# Day0_Rahmadi_Rizki_S_Pandia.net
KiCad netlist of a schematic drawn in EAGLE
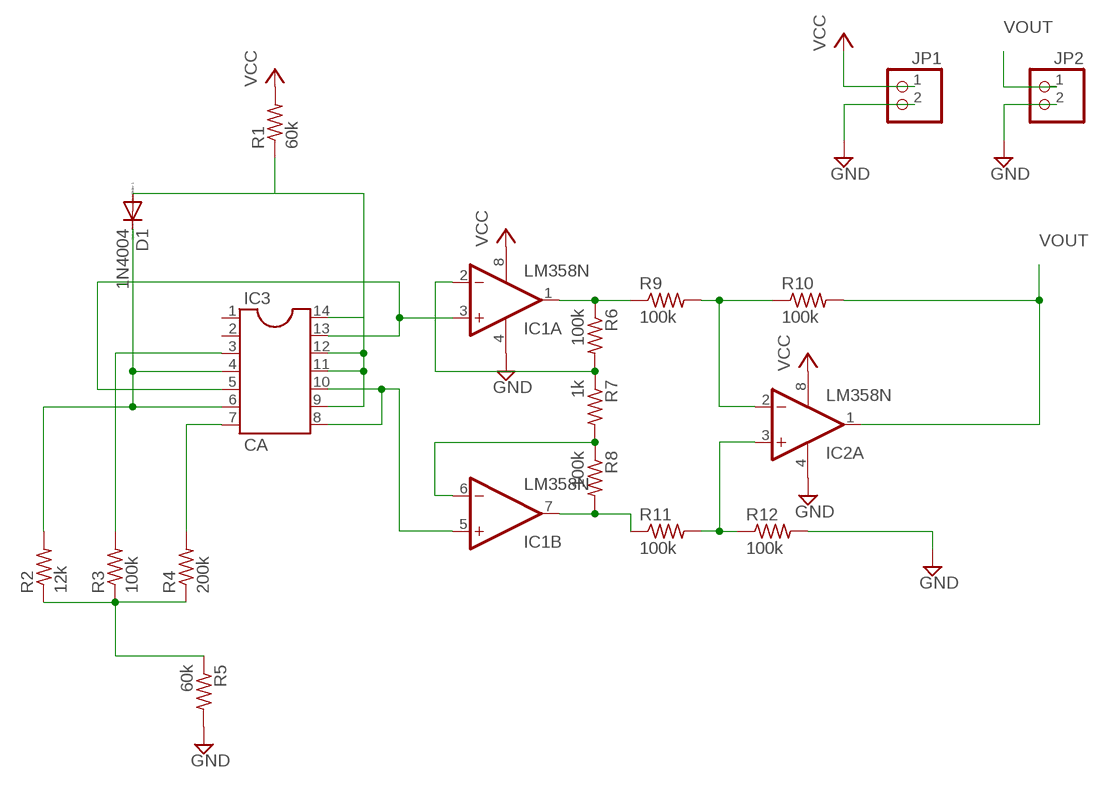
[diagram p0: schematic, sheet 1]

(export (version "E")
  (design (tool "Eeschema 10.0.6"))
  (components
    (comp (ref "D1")
      (value "1N4004")
      (footprint "eagle-import:D-7.5")
      (libsource (lib "eagle-import") (part "DIODE-D-7.5"))
    )
    (comp (ref "IC1")
      (value "LM358N")
      (footprint "eagle-import:DIL08")
      (libsource (lib "eagle-import") (part "LM358N"))
    )
    (comp (ref "IC2")
      (value "LM358N")
      (footprint "eagle-import:DIL08")
      (libsource (lib "eagle-import") (part "LM358N"))
    )
    (comp (ref "IC3")
      (value "CA")
      (footprint "eagle-import:DIL14")
      (libsource (lib "eagle-import") (part "DIL14"))
    )
    (comp (ref "JP1")
      (value "PINHD-1X2")
      (footprint "eagle-import:1X02")
      (libsource (lib "eagle-import") (part "PINHD-1X2"))
    )
    (comp (ref "JP2")
      (value "PINHD-1X2")
      (footprint "eagle-import:1X02")
      (libsource (lib "eagle-import") (part "PINHD-1X2"))
    )
    (comp (ref "R1")
      (value "60k")
      (footprint "eagle-import:0204_7")
      (libsource (lib "eagle-import") (part "R-US_0204/7"))
    )
    (comp (ref "R2")
      (value "12k")
      (footprint "eagle-import:0204_7")
      (libsource (lib "eagle-import") (part "R-US_0204/7"))
    )
    (comp (ref "R3")
      (value "100k")
      (footprint "eagle-import:0204_7")
      (libsource (lib "eagle-import") (part "R-US_0204/7"))
    )
    (comp (ref "R4")
      (value "200k")
      (footprint "eagle-import:0204_7")
      (libsource (lib "eagle-import") (part "R-US_0204/7"))
    )
    (comp (ref "R5")
      (value "60k")
      (footprint "eagle-import:0204_7")
      (libsource (lib "eagle-import") (part "R-US_0204/7"))
    )
    (comp (ref "R6")
      (value "100k")
      (footprint "eagle-import:0204_7")
      (libsource (lib "eagle-import") (part "R-US_0204/7"))
    )
    (comp (ref "R7")
      (value "1k")
      (footprint "eagle-import:0204_7")
      (libsource (lib "eagle-import") (part "R-US_0204/7"))
    )
    (comp (ref "R8")
      (value "100k")
      (footprint "eagle-import:0204_7")
      (libsource (lib "eagle-import") (part "R-US_0204/7"))
    )
    (comp (ref "R9")
      (value "100k")
      (footprint "eagle-import:0204_7")
      (libsource (lib "eagle-import") (part "R-US_0204/7"))
    )
    (comp (ref "R10")
      (value "100k")
      (footprint "eagle-import:0204_7")
      (libsource (lib "eagle-import") (part "R-US_0204/7"))
    )
    (comp (ref "R11")
      (value "100k")
      (footprint "eagle-import:0204_7")
      (libsource (lib "eagle-import") (part "R-US_0204/7"))
    )
    (comp (ref "R12")
      (value "100k")
      (footprint "eagle-import:0204_7")
      (libsource (lib "eagle-import") (part "R-US_0204/7"))
    )
  )
  (nets
    (net (code "1") (name "/VOUT") (class "Default")
      (node (ref "IC2") (pin "1") (pinfunction "OUT_1") (pintype "output"))
      (node (ref "JP2") (pin "1") (pinfunction "1_1") (pintype "passive"))
      (node (ref "R10") (pin "2") (pinfunction "2_2") (pintype "passive"))
    )
    (net (code "2") (name "GND") (class "Default")
      (node (ref "IC1") (pin "4") (pinfunction "V-_4") (pintype "power_in"))
      (node (ref "IC2") (pin "4") (pinfunction "V-_4") (pintype "power_in"))
      (node (ref "JP1") (pin "2") (pinfunction "2_2") (pintype "passive"))
      (node (ref "JP2") (pin "2") (pinfunction "2_2") (pintype "passive"))
      (node (ref "R12") (pin "2") (pinfunction "2_2") (pintype "passive"))
      (node (ref "R5") (pin "2") (pinfunction "2_2") (pintype "passive"))
    )
    (net (code "3") (name "Net-(D1-PadA)") (class "Default")
      (node (ref "D1") (pin "A") (pinfunction "A_A") (pintype "passive"))
      (node (ref "IC3") (pin "11") (pinfunction "11_11") (pintype "passive"))
      (node (ref "IC3") (pin "12") (pinfunction "12_12") (pintype "passive"))
      (node (ref "IC3") (pin "14") (pinfunction "14_14") (pintype "passive"))
      (node (ref "IC3") (pin "9") (pinfunction "9_9") (pintype "passive"))
      (node (ref "R1") (pin "1") (pinfunction "1_1") (pintype "passive"))
    )
    (net (code "4") (name "Net-(D1-PadC)") (class "Default")
      (node (ref "D1") (pin "C") (pinfunction "C_C") (pintype "passive"))
      (node (ref "IC3") (pin "4") (pinfunction "4_4") (pintype "passive"))
      (node (ref "IC3") (pin "6") (pinfunction "6_6") (pintype "passive"))
      (node (ref "R2") (pin "2") (pinfunction "2_2") (pintype "passive"))
    )
    (net (code "5") (name "Net-(IC1A-+IN)") (class "Default")
      (node (ref "IC1") (pin "3") (pinfunction "+IN_3") (pintype "input"))
      (node (ref "IC3") (pin "13") (pinfunction "13_13") (pintype "passive"))
      (node (ref "IC3") (pin "5") (pinfunction "5_5") (pintype "passive"))
    )
    (net (code "6") (name "Net-(IC1A--IN)") (class "Default")
      (node (ref "IC1") (pin "2") (pinfunction "-IN_2") (pintype "input"))
      (node (ref "R6") (pin "2") (pinfunction "2_2") (pintype "passive"))
      (node (ref "R7") (pin "1") (pinfunction "1_1") (pintype "passive"))
    )
    (net (code "7") (name "Net-(IC1A-OUT)") (class "Default")
      (node (ref "IC1") (pin "1") (pinfunction "OUT_1") (pintype "output"))
      (node (ref "R6") (pin "1") (pinfunction "1_1") (pintype "passive"))
      (node (ref "R9") (pin "1") (pinfunction "1_1") (pintype "passive"))
    )
    (net (code "8") (name "Net-(IC1B-+IN)") (class "Default")
      (node (ref "IC1") (pin "5") (pinfunction "+IN_5") (pintype "input"))
      (node (ref "IC3") (pin "10") (pinfunction "10_10") (pintype "passive"))
      (node (ref "IC3") (pin "8") (pinfunction "8_8") (pintype "passive"))
    )
    (net (code "9") (name "Net-(IC1B--IN)") (class "Default")
      (node (ref "IC1") (pin "6") (pinfunction "-IN_6") (pintype "input"))
      (node (ref "R7") (pin "2") (pinfunction "2_2") (pintype "passive"))
      (node (ref "R8") (pin "1") (pinfunction "1_1") (pintype "passive"))
    )
    (net (code "10") (name "Net-(IC1B-OUT)") (class "Default")
      (node (ref "IC1") (pin "7") (pinfunction "OUT_7") (pintype "output"))
      (node (ref "R11") (pin "1") (pinfunction "1_1") (pintype "passive"))
      (node (ref "R8") (pin "2") (pinfunction "2_2") (pintype "passive"))
    )
    (net (code "11") (name "Net-(IC2A-+IN)") (class "Default")
      (node (ref "IC2") (pin "3") (pinfunction "+IN_3") (pintype "input"))
      (node (ref "R11") (pin "2") (pinfunction "2_2") (pintype "passive"))
      (node (ref "R12") (pin "1") (pinfunction "1_1") (pintype "passive"))
    )
    (net (code "12") (name "Net-(IC2A--IN)") (class "Default")
      (node (ref "IC2") (pin "2") (pinfunction "-IN_2") (pintype "input"))
      (node (ref "R10") (pin "1") (pinfunction "1_1") (pintype "passive"))
      (node (ref "R9") (pin "2") (pinfunction "2_2") (pintype "passive"))
    )
    (net (code "13") (name "Net-(IC3-Pad3)") (class "Default")
      (node (ref "IC3") (pin "3") (pinfunction "3_3") (pintype "passive"))
      (node (ref "R3") (pin "2") (pinfunction "2_2") (pintype "passive"))
    )
    (net (code "14") (name "Net-(IC3-Pad7)") (class "Default")
      (node (ref "IC3") (pin "7") (pinfunction "7_7") (pintype "passive"))
      (node (ref "R4") (pin "2") (pinfunction "2_2") (pintype "passive"))
    )
    (net (code "15") (name "Net-(R2-Pad1)") (class "Default")
      (node (ref "R2") (pin "1") (pinfunction "1_1") (pintype "passive"))
      (node (ref "R3") (pin "1") (pinfunction "1_1") (pintype "passive"))
      (node (ref "R4") (pin "1") (pinfunction "1_1") (pintype "passive"))
      (node (ref "R5") (pin "1") (pinfunction "1_1") (pintype "passive"))
    )
    (net (code "16") (name "VCC") (class "Default")
      (node (ref "IC1") (pin "8") (pinfunction "V+_8") (pintype "power_in"))
      (node (ref "IC2") (pin "8") (pinfunction "V+_8") (pintype "power_in"))
      (node (ref "JP1") (pin "1") (pinfunction "1_1") (pintype "passive"))
      (node (ref "R1") (pin "2") (pinfunction "2_2") (pintype "passive"))
    )
    (net (code "17") (name "unconnected-(IC3-Pad1)") (class "Default")
      (node (ref "IC3") (pin "1") (pinfunction "1_1") (pintype "passive"))
    )
    (net (code "18") (name "unconnected-(IC3-Pad2)") (class "Default")
      (node (ref "IC3") (pin "2") (pinfunction "2_2") (pintype "passive"))
    )
  )
)
